# dcdc_na_akkum.net
KiCad netlist of a schematic drawn in Altium Designer
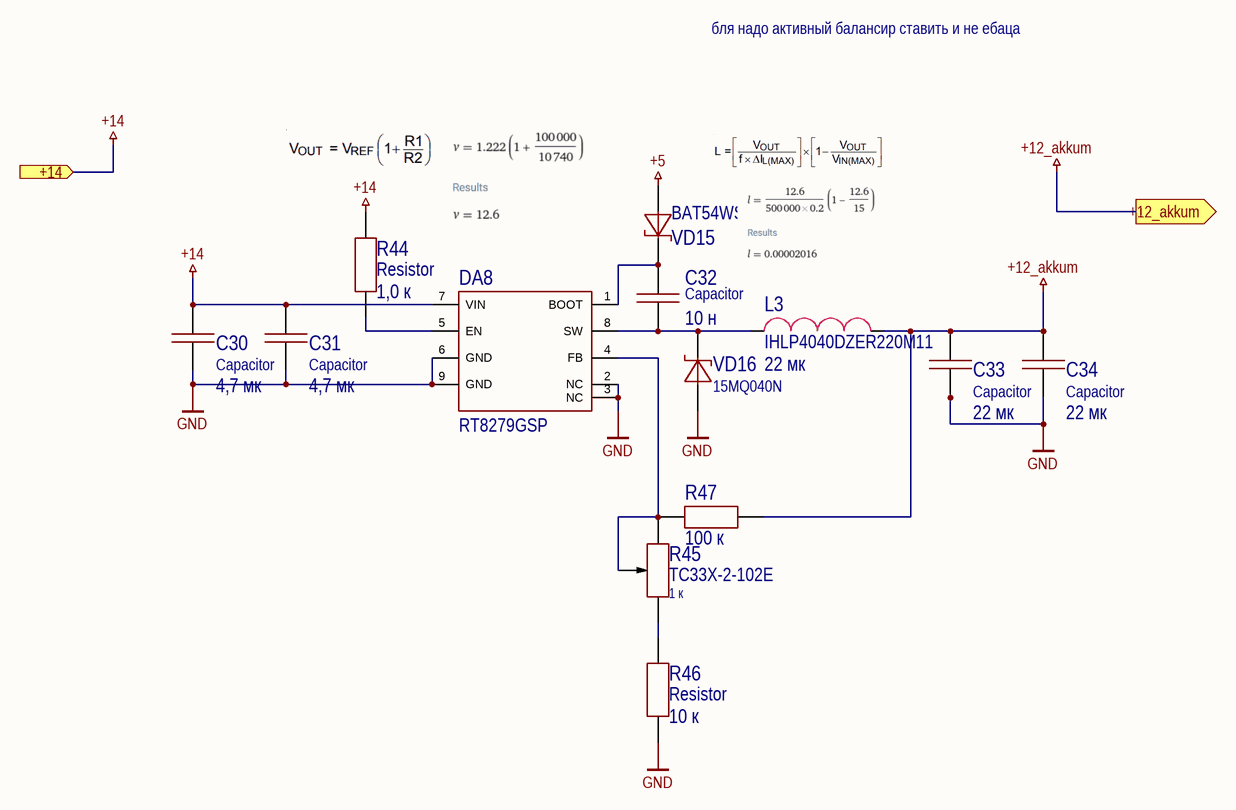
[diagram p0: dcdc_na_akkum.SchDoc]

(export (version "E")
  (design (tool "Eeschema 10.0.6"))
  (components
    (comp (ref "C30")
      (value "Capacitor")
      (footprint "1206C")
      (description "Конденсатор")
      (fields
        (field (name "ALTIUM_VALUE") "4,7 мк")
        (field (name "PART NUMBER") "Capacitor_4,7u_10_50V_X7R_1206C")
        (field (name "TOLERANCE") "0,1")
      )
      (libsource (lib "Hydrolib") (part "Capacitor"))
    )
    (comp (ref "C31")
      (value "Capacitor")
      (footprint "1206C")
      (description "Конденсатор")
      (fields
        (field (name "ALTIUM_VALUE") "4,7 мк")
        (field (name "PART NUMBER") "Capacitor_4,7u_10_50V_X7R_1206C")
        (field (name "TOLERANCE") "0,1")
      )
      (libsource (lib "Hydrolib") (part "Capacitor"))
    )
    (comp (ref "C32")
      (value "Capacitor")
      (footprint "0603C")
      (description "Конденсатор")
      (fields
        (field (name "ALTIUM_VALUE") "10 н")
        (field (name "PART NUMBER") "Capacitor_10n_10_50V_X7R_0603C")
        (field (name "TOLERANCE") "0,1")
      )
      (libsource (lib "Hydrolib") (part "Capacitor"))
    )
    (comp (ref "C33")
      (value "Capacitor")
      (footprint "1210C")
      (description "Конденсатор")
      (fields
        (field (name "ALTIUM_VALUE") "22 мк")
        (field (name "PART NUMBER") "Capacitor_22u_10_25V_X7R_1210C")
        (field (name "TOLERANCE") "0,1")
      )
      (libsource (lib "Hydrolib") (part "Capacitor"))
    )
    (comp (ref "C34")
      (value "Capacitor")
      (footprint "1210C")
      (description "Конденсатор")
      (fields
        (field (name "ALTIUM_VALUE") "22 мк")
        (field (name "PART NUMBER") "Capacitor_22u_10_25V_X7R_1210C")
        (field (name "TOLERANCE") "0,1")
      )
      (libsource (lib "Hydrolib") (part "Capacitor"))
    )
    (comp (ref "DA8")
      (value "RT8279GSP")
      (footprint "8SOP(Exposed_Pad)")
      (description "Преобразователь постоянного тока понижающий подстраиваемый выход 5А")
      (libsource (lib "Hydrolib") (part "RT8279GSP"))
    )
    (comp (ref "L3")
      (value "IHLP4040DZER220M11")
      (footprint "IHLP-4040")
      (description "ЧИП-индуктивность экранированная 22мкГн ±20% 5A 66мОм 4040 лента на катушке")
      (fields (field (name "ALTIUM_VALUE") "22 мк"))
      (libsource (lib "Hydrolib") (part "Inductance"))
    )
    (comp (ref "R44")
      (value "Resistor")
      (footprint "0603R")
      (description "Резистор номиналом 1,0 кОм и точностью 1%")
      (fields
        (field (name "ALTIUM_VALUE") "1,0 к")
        (field (name "PART NUMBER") "Resistor_1.0k_1_0603")
        (field (name "TOLERANCE") "1%")
      )
      (libsource (lib "") (part "Resistor_1"))
    )
    (comp (ref "R45")
      (value "TC33X-2-102E")
      (footprint "3mm_trim")
      (description "Потенциометр керметный 1кОм 0.1Вт для поверхностного монтажа")
      (fields (field (name "ALTIUM_VALUE") "1 к") (field (name "TOLERANCE") "50%"))
      (libsource (lib "Hydrolib") (part "trim_res"))
    )
    (comp (ref "R46")
      (value "Resistor")
      (footprint "0603R")
      (description "Резистор номиналом 10 кОм и точностью 1%")
      (fields
        (field (name "ALTIUM_VALUE") "10 к")
        (field (name "PART NUMBER") "Resistor_10k_1_0603")
        (field (name "TOLERANCE") "1%")
      )
      (libsource (lib "") (part "Resistor_1"))
    )
    (comp (ref "R47")
      (value "100 к")
      (footprint "0603R")
      (description "Резистор номиналом 100 кОм и точностью 1%")
      (fields (field (name "PART NUMBER") "Resistor_100k_1_0603") (field (name "TOLERANCE") "1%"))
      (libsource (lib "Hydrolib") (part "Resistor"))
    )
    (comp (ref "VD15")
      (value "BAT54WS")
      (footprint "SOD-323")
      (description "Диод шоттки на 30 В, ном. ток 0.2 А")
      (libsource (lib "Hydrolib") (part "Schottky_diode"))
    )
    (comp (ref "VD16")
      (value "15MQ040N")
      (footprint "SMA")
      (description "Диод шоттки на 40 В, ном. ток 2.1 А")
      (libsource (lib "Hydrolib") (part "Schottky_diode"))
    )
  )
  (nets
    (net (code "1") (name "+5") (class "Default")
      (node (ref "VD15") (pin "1") (pinfunction "1_1") (pintype "passive"))
    )
    (net (code "2") (name "+12_akkum") (class "Default")
      (node (ref "C33") (pin "2") (pinfunction "2_2") (pintype "passive"))
      (node (ref "C34") (pin "2") (pinfunction "2_2") (pintype "passive"))
      (node (ref "L3") (pin "2") (pinfunction "2_2") (pintype "passive"))
      (node (ref "R47") (pin "2") (pinfunction "2_2") (pintype "passive"))
    )
    (net (code "3") (name "+14") (class "Default")
      (node (ref "C30") (pin "2") (pinfunction "2_2") (pintype "passive"))
      (node (ref "C31") (pin "2") (pinfunction "2_2") (pintype "passive"))
      (node (ref "DA8") (pin "7") (pinfunction "VIN_7") (pintype "passive"))
      (node (ref "R44") (pin "2") (pinfunction "2_2") (pintype "passive"))
    )
    (net (code "4") (name "GND") (class "Default")
      (node (ref "C30") (pin "1") (pinfunction "1_1") (pintype "passive"))
      (node (ref "C31") (pin "1") (pinfunction "1_1") (pintype "passive"))
      (node (ref "C33") (pin "1") (pinfunction "1_1") (pintype "passive"))
      (node (ref "C34") (pin "1") (pinfunction "1_1") (pintype "passive"))
      (node (ref "DA8") (pin "2") (pinfunction "NC_2") (pintype "passive"))
      (node (ref "DA8") (pin "3") (pinfunction "NC_3") (pintype "passive"))
      (node (ref "DA8") (pin "6") (pinfunction "GND_6") (pintype "passive"))
      (node (ref "DA8") (pin "9") (pinfunction "GND_9") (pintype "passive"))
      (node (ref "R46") (pin "1") (pinfunction "1_1") (pintype "passive"))
      (node (ref "VD16") (pin "1") (pinfunction "1_1") (pintype "passive"))
    )
    (net (code "5") (name "Net-(DA8-BOOT)") (class "Default")
      (node (ref "C32") (pin "2") (pinfunction "2_2") (pintype "passive"))
      (node (ref "DA8") (pin "1") (pinfunction "BOOT_1") (pintype "passive"))
      (node (ref "VD15") (pin "2") (pinfunction "2_2") (pintype "passive"))
    )
    (net (code "6") (name "Net-(DA8-EN)") (class "Default")
      (node (ref "DA8") (pin "5") (pinfunction "EN_5") (pintype "passive"))
      (node (ref "R44") (pin "1") (pinfunction "1_1") (pintype "passive"))
    )
    (net (code "7") (name "Net-(DA8-FB)") (class "Default")
      (node (ref "DA8") (pin "4") (pinfunction "FB_4") (pintype "passive"))
      (node (ref "R45") (pin "2") (pinfunction "2_2") (pintype "passive"))
      (node (ref "R45") (pin "3") (pinfunction "3_3") (pintype "passive"))
      (node (ref "R47") (pin "1") (pinfunction "1_1") (pintype "passive"))
    )
    (net (code "8") (name "Net-(DA8-SW)") (class "Default")
      (node (ref "C32") (pin "1") (pinfunction "1_1") (pintype "passive"))
      (node (ref "DA8") (pin "8") (pinfunction "SW_8") (pintype "passive"))
      (node (ref "L3") (pin "1") (pinfunction "1_1") (pintype "passive"))
      (node (ref "VD16") (pin "2") (pinfunction "2_2") (pintype "passive"))
    )
    (net (code "9") (name "Net-(R45-Pad1)") (class "Default")
      (node (ref "R45") (pin "1") (pinfunction "1_1") (pintype "passive"))
      (node (ref "R46") (pin "2") (pinfunction "2_2") (pintype "passive"))
    )
  )
)
